# Edin_TinyPico_Nano.net
KiCad netlist of a schematic drawn in EAGLE
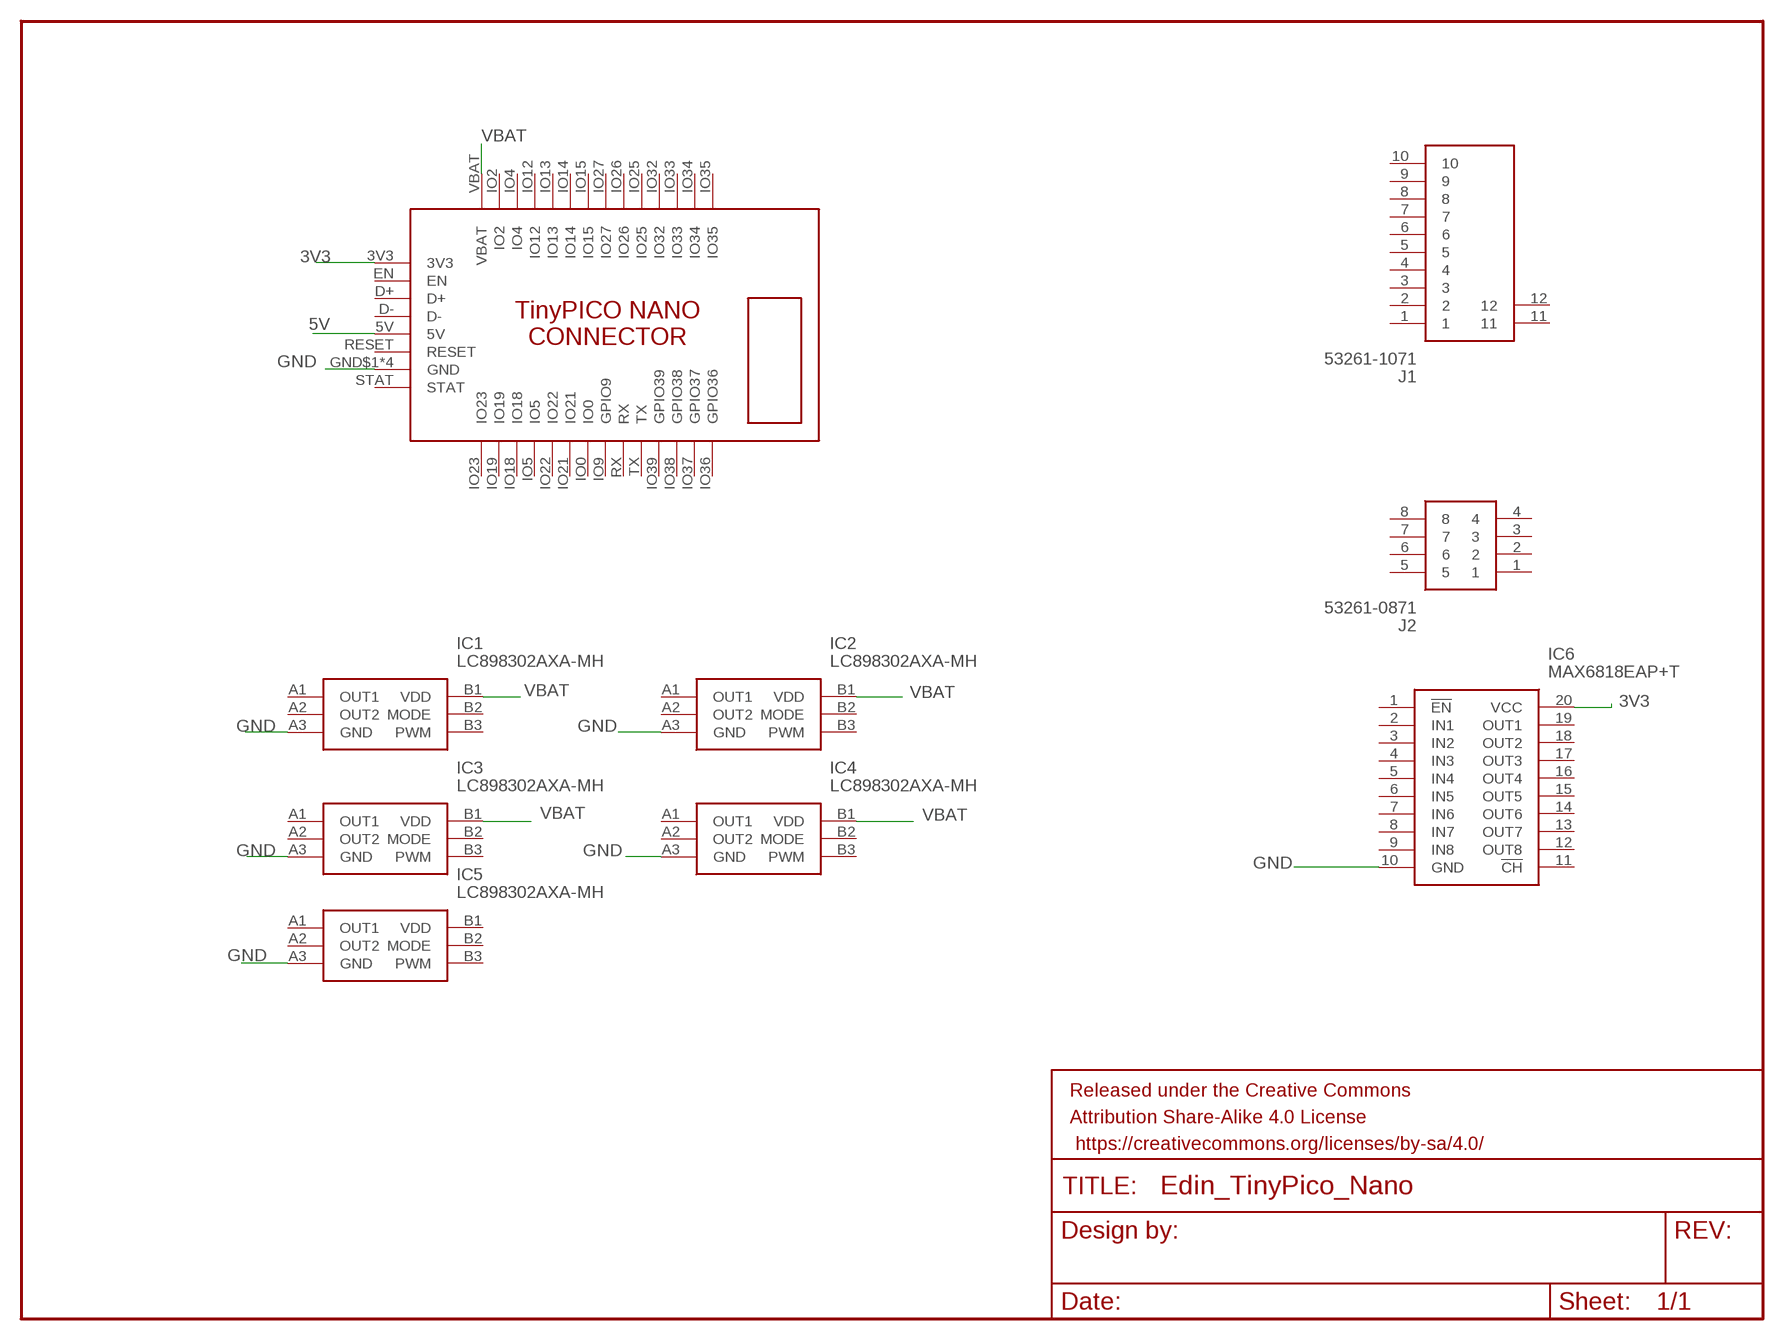
[diagram p0: schematic, sheet 1]

(export (version "E")
  (design (tool "Eeschema 10.0.6"))
  (components
    (comp (ref "FRAME1")
      (value "FRAME-LETTER")
      (footprint "eagle-import:CREATIVE_COMMONS")
      (libsource (lib "eagle-import") (part "FRAME-LETTER"))
    )
    (comp (ref "IC1")
      (value "LC898302AXA-MH")
      (footprint "eagle-import:BGA6C40P3X2_118X78X65")
      (fields (field (name "MOUSER_PART_NUMBER") "863-LC898302AXA-MH"))
      (libsource (lib "eagle-import") (part "LC898302AXA-MH"))
    )
    (comp (ref "IC2")
      (value "LC898302AXA-MH")
      (footprint "eagle-import:BGA6C40P3X2_118X78X65")
      (fields (field (name "MOUSER_PART_NUMBER") "863-LC898302AXA-MH"))
      (libsource (lib "eagle-import") (part "LC898302AXA-MH"))
    )
    (comp (ref "IC3")
      (value "LC898302AXA-MH")
      (footprint "eagle-import:BGA6C40P3X2_118X78X65")
      (fields (field (name "MOUSER_PART_NUMBER") "863-LC898302AXA-MH"))
      (libsource (lib "eagle-import") (part "LC898302AXA-MH"))
    )
    (comp (ref "IC4")
      (value "LC898302AXA-MH")
      (footprint "eagle-import:BGA6C40P3X2_118X78X65")
      (fields (field (name "MOUSER_PART_NUMBER") "863-LC898302AXA-MH"))
      (libsource (lib "eagle-import") (part "LC898302AXA-MH"))
    )
    (comp (ref "IC5")
      (value "LC898302AXA-MH")
      (footprint "eagle-import:BGA6C40P3X2_118X78X65")
      (fields (field (name "MOUSER_PART_NUMBER") "863-LC898302AXA-MH"))
      (libsource (lib "eagle-import") (part "LC898302AXA-MH"))
    )
    (comp (ref "IC6")
      (value "MAX6818EAP+T")
      (footprint "eagle-import:SOP65P778X199-20N")
      (fields (field (name "MOUSER_PART_NUMBER") "700-MAX6818EAPT"))
      (libsource (lib "eagle-import") (part "MAX6818EAP+T"))
    )
    (comp (ref "J1")
      (value "53261-1071")
      (footprint "eagle-import:532611071")
      (fields (field (name "MOUSER_PART_NUMBER") "538-53261-1071"))
      (libsource (lib "eagle-import") (part "53261-1071"))
    )
    (comp (ref "J2")
      (value "53261-0871")
      (footprint "eagle-import:53261-0871")
      (fields (field (name "MOUSER_PART_NUMBER") "538-53261-0871"))
      (libsource (lib "eagle-import") (part "53261-0871"))
    )
    (comp (ref "U$1")
      (value "TINYPICO-NANO-CONNECTOR")
      (footprint "eagle-import:TINYPICO-NANO-CONNECTOR")
      (libsource (lib "eagle-import") (part "TINYPICO-NANO-CONNECTOR"))
    )
  )
  (nets
    (net (code "1") (name "/3V3") (class "Default")
      (node (ref "IC6") (pin "20") (pinfunction "VCC_20") (pintype "power_in"))
      (node (ref "U$1") (pin "3V3") (pinfunction "3V3_3V3") (pintype "power_in"))
    )
    (net (code "2") (name "/5V") (class "Default")
      (node (ref "U$1") (pin "5V") (pinfunction "5V_5V") (pintype "power_in"))
    )
    (net (code "3") (name "/GND") (class "Default")
      (node (ref "IC1") (pin "A3") (pinfunction "GND_A3") (pintype "bidirectional"))
      (node (ref "IC2") (pin "A3") (pinfunction "GND_A3") (pintype "bidirectional"))
      (node (ref "IC3") (pin "A3") (pinfunction "GND_A3") (pintype "bidirectional"))
      (node (ref "IC4") (pin "A3") (pinfunction "GND_A3") (pintype "bidirectional"))
      (node (ref "IC5") (pin "A3") (pinfunction "GND_A3") (pintype "bidirectional"))
      (node (ref "IC6") (pin "10") (pinfunction "GND_10") (pintype "power_in"))
      (node (ref "U$1") (pin "GND$1") (pinfunction "GND_GND$1") (pintype "power_in"))
      (node (ref "U$1") (pin "GND$2") (pinfunction "GND_GND$2") (pintype "power_in"))
      (node (ref "U$1") (pin "GND$3") (pinfunction "GND_GND$3") (pintype "power_in"))
      (node (ref "U$1") (pin "GND$4") (pinfunction "GND_GND$4") (pintype "power_in"))
    )
    (net (code "4") (name "/VBAT") (class "Default")
      (node (ref "IC1") (pin "B1") (pinfunction "VDD_B1") (pintype "bidirectional"))
      (node (ref "IC2") (pin "B1") (pinfunction "VDD_B1") (pintype "bidirectional"))
      (node (ref "IC3") (pin "B1") (pinfunction "VDD_B1") (pintype "bidirectional"))
      (node (ref "IC4") (pin "B1") (pinfunction "VDD_B1") (pintype "bidirectional"))
      (node (ref "U$1") (pin "VBAT") (pinfunction "VBAT_VBAT") (pintype "power_in"))
    )
    (net (code "5") (name "unconnected-(IC1-MODE-PadB2)") (class "Default")
      (node (ref "IC1") (pin "B2") (pinfunction "MODE_B2") (pintype "bidirectional"))
    )
    (net (code "6") (name "unconnected-(IC1-OUT1-PadA1)") (class "Default")
      (node (ref "IC1") (pin "A1") (pinfunction "OUT1_A1") (pintype "bidirectional"))
    )
    (net (code "7") (name "unconnected-(IC1-OUT2-PadA2)") (class "Default")
      (node (ref "IC1") (pin "A2") (pinfunction "OUT2_A2") (pintype "bidirectional"))
    )
    (net (code "8") (name "unconnected-(IC1-PWM-PadB3)") (class "Default")
      (node (ref "IC1") (pin "B3") (pinfunction "PWM_B3") (pintype "bidirectional"))
    )
    (net (code "9") (name "unconnected-(IC2-MODE-PadB2)") (class "Default")
      (node (ref "IC2") (pin "B2") (pinfunction "MODE_B2") (pintype "bidirectional"))
    )
    (net (code "10") (name "unconnected-(IC2-OUT1-PadA1)") (class "Default")
      (node (ref "IC2") (pin "A1") (pinfunction "OUT1_A1") (pintype "bidirectional"))
    )
    (net (code "11") (name "unconnected-(IC2-OUT2-PadA2)") (class "Default")
      (node (ref "IC2") (pin "A2") (pinfunction "OUT2_A2") (pintype "bidirectional"))
    )
    (net (code "12") (name "unconnected-(IC2-PWM-PadB3)") (class "Default")
      (node (ref "IC2") (pin "B3") (pinfunction "PWM_B3") (pintype "bidirectional"))
    )
    (net (code "13") (name "unconnected-(IC3-MODE-PadB2)") (class "Default")
      (node (ref "IC3") (pin "B2") (pinfunction "MODE_B2") (pintype "bidirectional"))
    )
    (net (code "14") (name "unconnected-(IC3-OUT1-PadA1)") (class "Default")
      (node (ref "IC3") (pin "A1") (pinfunction "OUT1_A1") (pintype "bidirectional"))
    )
    (net (code "15") (name "unconnected-(IC3-OUT2-PadA2)") (class "Default")
      (node (ref "IC3") (pin "A2") (pinfunction "OUT2_A2") (pintype "bidirectional"))
    )
    (net (code "16") (name "unconnected-(IC3-PWM-PadB3)") (class "Default")
      (node (ref "IC3") (pin "B3") (pinfunction "PWM_B3") (pintype "bidirectional"))
    )
    (net (code "17") (name "unconnected-(IC4-MODE-PadB2)") (class "Default")
      (node (ref "IC4") (pin "B2") (pinfunction "MODE_B2") (pintype "bidirectional"))
    )
    (net (code "18") (name "unconnected-(IC4-OUT1-PadA1)") (class "Default")
      (node (ref "IC4") (pin "A1") (pinfunction "OUT1_A1") (pintype "bidirectional"))
    )
    (net (code "19") (name "unconnected-(IC4-OUT2-PadA2)") (class "Default")
      (node (ref "IC4") (pin "A2") (pinfunction "OUT2_A2") (pintype "bidirectional"))
    )
    (net (code "20") (name "unconnected-(IC4-PWM-PadB3)") (class "Default")
      (node (ref "IC4") (pin "B3") (pinfunction "PWM_B3") (pintype "bidirectional"))
    )
    (net (code "21") (name "unconnected-(IC5-MODE-PadB2)") (class "Default")
      (node (ref "IC5") (pin "B2") (pinfunction "MODE_B2") (pintype "bidirectional"))
    )
    (net (code "22") (name "unconnected-(IC5-OUT1-PadA1)") (class "Default")
      (node (ref "IC5") (pin "A1") (pinfunction "OUT1_A1") (pintype "bidirectional"))
    )
    (net (code "23") (name "unconnected-(IC5-OUT2-PadA2)") (class "Default")
      (node (ref "IC5") (pin "A2") (pinfunction "OUT2_A2") (pintype "bidirectional"))
    )
    (net (code "24") (name "unconnected-(IC5-PWM-PadB3)") (class "Default")
      (node (ref "IC5") (pin "B3") (pinfunction "PWM_B3") (pintype "bidirectional"))
    )
    (net (code "25") (name "unconnected-(IC5-VDD-PadB1)") (class "Default")
      (node (ref "IC5") (pin "B1") (pinfunction "VDD_B1") (pintype "bidirectional"))
    )
    (net (code "26") (name "unconnected-(IC6-IN1-Pad2)") (class "Default")
      (node (ref "IC6") (pin "2") (pinfunction "IN1_2") (pintype "input"))
    )
    (net (code "27") (name "unconnected-(IC6-IN2-Pad3)") (class "Default")
      (node (ref "IC6") (pin "3") (pinfunction "IN2_3") (pintype "input"))
    )
    (net (code "28") (name "unconnected-(IC6-IN3-Pad4)") (class "Default")
      (node (ref "IC6") (pin "4") (pinfunction "IN3_4") (pintype "input"))
    )
    (net (code "29") (name "unconnected-(IC6-IN4-Pad5)") (class "Default")
      (node (ref "IC6") (pin "5") (pinfunction "IN4_5") (pintype "input"))
    )
    (net (code "30") (name "unconnected-(IC6-IN5-Pad6)") (class "Default")
      (node (ref "IC6") (pin "6") (pinfunction "IN5_6") (pintype "input"))
    )
    (net (code "31") (name "unconnected-(IC6-IN6-Pad7)") (class "Default")
      (node (ref "IC6") (pin "7") (pinfunction "IN6_7") (pintype "input"))
    )
    (net (code "32") (name "unconnected-(IC6-IN7-Pad8)") (class "Default")
      (node (ref "IC6") (pin "8") (pinfunction "IN7_8") (pintype "input"))
    )
    (net (code "33") (name "unconnected-(IC6-IN8-Pad9)") (class "Default")
      (node (ref "IC6") (pin "9") (pinfunction "IN8_9") (pintype "input"))
    )
    (net (code "34") (name "unconnected-(IC6-OUT1-Pad19)") (class "Default")
      (node (ref "IC6") (pin "19") (pinfunction "OUT1_19") (pintype "output"))
    )
    (net (code "35") (name "unconnected-(IC6-OUT2-Pad18)") (class "Default")
      (node (ref "IC6") (pin "18") (pinfunction "OUT2_18") (pintype "output"))
    )
    (net (code "36") (name "unconnected-(IC6-OUT3-Pad17)") (class "Default")
      (node (ref "IC6") (pin "17") (pinfunction "OUT3_17") (pintype "output"))
    )
    (net (code "37") (name "unconnected-(IC6-OUT4-Pad16)") (class "Default")
      (node (ref "IC6") (pin "16") (pinfunction "OUT4_16") (pintype "output"))
    )
    (net (code "38") (name "unconnected-(IC6-OUT5-Pad15)") (class "Default")
      (node (ref "IC6") (pin "15") (pinfunction "OUT5_15") (pintype "output"))
    )
    (net (code "39") (name "unconnected-(IC6-OUT6-Pad14)") (class "Default")
      (node (ref "IC6") (pin "14") (pinfunction "OUT6_14") (pintype "output"))
    )
    (net (code "40") (name "unconnected-(IC6-OUT7-Pad13)") (class "Default")
      (node (ref "IC6") (pin "13") (pinfunction "OUT7_13") (pintype "output"))
    )
    (net (code "41") (name "unconnected-(IC6-OUT8-Pad12)") (class "Default")
      (node (ref "IC6") (pin "12") (pinfunction "OUT8_12") (pintype "output"))
    )
    (net (code "42") (name "unconnected-(IC6-~{CH}-Pad11)") (class "Default")
      (node (ref "IC6") (pin "11") (pinfunction "~{CH}_11") (pintype "output"))
    )
    (net (code "43") (name "unconnected-(IC6-~{EN}-Pad1)") (class "Default")
      (node (ref "IC6") (pin "1") (pinfunction "~{EN}_1") (pintype "input"))
    )
    (net (code "44") (name "unconnected-(J1-Pad1)") (class "Default")
      (node (ref "J1") (pin "1") (pinfunction "1_1") (pintype "bidirectional"))
    )
    (net (code "45") (name "unconnected-(J1-Pad2)") (class "Default")
      (node (ref "J1") (pin "2") (pinfunction "2_2") (pintype "bidirectional"))
    )
    (net (code "46") (name "unconnected-(J1-Pad3)") (class "Default")
      (node (ref "J1") (pin "3") (pinfunction "3_3") (pintype "bidirectional"))
    )
    (net (code "47") (name "unconnected-(J1-Pad4)") (class "Default")
      (node (ref "J1") (pin "4") (pinfunction "4_4") (pintype "bidirectional"))
    )
    (net (code "48") (name "unconnected-(J1-Pad5)") (class "Default")
      (node (ref "J1") (pin "5") (pinfunction "5_5") (pintype "bidirectional"))
    )
    (net (code "49") (name "unconnected-(J1-Pad6)") (class "Default")
      (node (ref "J1") (pin "6") (pinfunction "6_6") (pintype "bidirectional"))
    )
    (net (code "50") (name "unconnected-(J1-Pad7)") (class "Default")
      (node (ref "J1") (pin "7") (pinfunction "7_7") (pintype "bidirectional"))
    )
    (net (code "51") (name "unconnected-(J1-Pad8)") (class "Default")
      (node (ref "J1") (pin "8") (pinfunction "8_8") (pintype "bidirectional"))
    )
    (net (code "52") (name "unconnected-(J1-Pad9)") (class "Default")
      (node (ref "J1") (pin "9") (pinfunction "9_9") (pintype "bidirectional"))
    )
    (net (code "53") (name "unconnected-(J1-Pad10)") (class "Default")
      (node (ref "J1") (pin "10") (pinfunction "10_10") (pintype "bidirectional"))
    )
    (net (code "54") (name "unconnected-(J1-Pad11)") (class "Default")
      (node (ref "J1") (pin "11") (pinfunction "11_11") (pintype "bidirectional"))
    )
    (net (code "55") (name "unconnected-(J1-Pad12)") (class "Default")
      (node (ref "J1") (pin "12") (pinfunction "12_12") (pintype "bidirectional"))
    )
    (net (code "56") (name "unconnected-(J2-Pad1)") (class "Default")
      (node (ref "J2") (pin "1") (pinfunction "1_1") (pintype "bidirectional"))
    )
    (net (code "57") (name "unconnected-(J2-Pad2)") (class "Default")
      (node (ref "J2") (pin "2") (pinfunction "2_2") (pintype "bidirectional"))
    )
    (net (code "58") (name "unconnected-(J2-Pad3)") (class "Default")
      (node (ref "J2") (pin "3") (pinfunction "3_3") (pintype "bidirectional"))
    )
    (net (code "59") (name "unconnected-(J2-Pad4)") (class "Default")
      (node (ref "J2") (pin "4") (pinfunction "4_4") (pintype "bidirectional"))
    )
    (net (code "60") (name "unconnected-(J2-Pad5)") (class "Default")
      (node (ref "J2") (pin "5") (pinfunction "5_5") (pintype "bidirectional"))
    )
    (net (code "61") (name "unconnected-(J2-Pad6)") (class "Default")
      (node (ref "J2") (pin "6") (pinfunction "6_6") (pintype "bidirectional"))
    )
    (net (code "62") (name "unconnected-(J2-Pad7)") (class "Default")
      (node (ref "J2") (pin "7") (pinfunction "7_7") (pintype "bidirectional"))
    )
    (net (code "63") (name "unconnected-(J2-Pad8)") (class "Default")
      (node (ref "J2") (pin "8") (pinfunction "8_8") (pintype "bidirectional"))
    )
    (net (code "64") (name "unconnected-(U$1-GPIO9-PadIO9)") (class "Default")
      (node (ref "U$1") (pin "IO9") (pinfunction "GPIO9_IO9") (pintype "bidirectional"))
    )
    (net (code "65") (name "unconnected-(U$1-GPIO36-PadIO36)") (class "Default")
      (node (ref "U$1") (pin "IO36") (pinfunction "GPIO36_IO36") (pintype "bidirectional"))
    )
    (net (code "66") (name "unconnected-(U$1-GPIO37-PadIO37)") (class "Default")
      (node (ref "U$1") (pin "IO37") (pinfunction "GPIO37_IO37") (pintype "bidirectional"))
    )
    (net (code "67") (name "unconnected-(U$1-GPIO38-PadIO38)") (class "Default")
      (node (ref "U$1") (pin "IO38") (pinfunction "GPIO38_IO38") (pintype "bidirectional"))
    )
    (net (code "68") (name "unconnected-(U$1-GPIO39-PadIO39)") (class "Default")
      (node (ref "U$1") (pin "IO39") (pinfunction "GPIO39_IO39") (pintype "bidirectional"))
    )
    (net (code "69") (name "unconnected-(U$1-PadD+)") (class "Default")
      (node (ref "U$1") (pin "D+") (pinfunction "D+_D+") (pintype "bidirectional"))
    )
    (net (code "70") (name "unconnected-(U$1-PadD-)") (class "Default")
      (node (ref "U$1") (pin "D-") (pinfunction "D-_D-") (pintype "bidirectional"))
    )
    (net (code "71") (name "unconnected-(U$1-PadEN)") (class "Default")
      (node (ref "U$1") (pin "EN") (pinfunction "EN_EN") (pintype "input"))
    )
    (net (code "72") (name "unconnected-(U$1-PadIO0)") (class "Default")
      (node (ref "U$1") (pin "IO0") (pinfunction "IO0_IO0") (pintype "bidirectional"))
    )
    (net (code "73") (name "unconnected-(U$1-PadIO2)") (class "Default")
      (node (ref "U$1") (pin "IO2") (pinfunction "IO2_IO2") (pintype "bidirectional"))
    )
    (net (code "74") (name "unconnected-(U$1-PadIO4)") (class "Default")
      (node (ref "U$1") (pin "IO4") (pinfunction "IO4_IO4") (pintype "bidirectional"))
    )
    (net (code "75") (name "unconnected-(U$1-PadIO5)") (class "Default")
      (node (ref "U$1") (pin "IO5") (pinfunction "IO5_IO5") (pintype "bidirectional"))
    )
    (net (code "76") (name "unconnected-(U$1-PadIO12)") (class "Default")
      (node (ref "U$1") (pin "IO12") (pinfunction "IO12_IO12") (pintype "bidirectional"))
    )
    (net (code "77") (name "unconnected-(U$1-PadIO13)") (class "Default")
      (node (ref "U$1") (pin "IO13") (pinfunction "IO13_IO13") (pintype "bidirectional"))
    )
    (net (code "78") (name "unconnected-(U$1-PadIO14)") (class "Default")
      (node (ref "U$1") (pin "IO14") (pinfunction "IO14_IO14") (pintype "bidirectional"))
    )
    (net (code "79") (name "unconnected-(U$1-PadIO15)") (class "Default")
      (node (ref "U$1") (pin "IO15") (pinfunction "IO15_IO15") (pintype "bidirectional"))
    )
    (net (code "80") (name "unconnected-(U$1-PadIO18)") (class "Default")
      (node (ref "U$1") (pin "IO18") (pinfunction "IO18_IO18") (pintype "bidirectional"))
    )
    (net (code "81") (name "unconnected-(U$1-PadIO19)") (class "Default")
      (node (ref "U$1") (pin "IO19") (pinfunction "IO19_IO19") (pintype "bidirectional"))
    )
    (net (code "82") (name "unconnected-(U$1-PadIO21)") (class "Default")
      (node (ref "U$1") (pin "IO21") (pinfunction "IO21_IO21") (pintype "bidirectional"))
    )
    (net (code "83") (name "unconnected-(U$1-PadIO22)") (class "Default")
      (node (ref "U$1") (pin "IO22") (pinfunction "IO22_IO22") (pintype "bidirectional"))
    )
    (net (code "84") (name "unconnected-(U$1-PadIO23)") (class "Default")
      (node (ref "U$1") (pin "IO23") (pinfunction "IO23_IO23") (pintype "bidirectional"))
    )
    (net (code "85") (name "unconnected-(U$1-PadIO25)") (class "Default")
      (node (ref "U$1") (pin "IO25") (pinfunction "IO25_IO25") (pintype "bidirectional"))
    )
    (net (code "86") (name "unconnected-(U$1-PadIO26)") (class "Default")
      (node (ref "U$1") (pin "IO26") (pinfunction "IO26_IO26") (pintype "bidirectional"))
    )
    (net (code "87") (name "unconnected-(U$1-PadIO27)") (class "Default")
      (node (ref "U$1") (pin "IO27") (pinfunction "IO27_IO27") (pintype "bidirectional"))
    )
    (net (code "88") (name "unconnected-(U$1-PadIO32)") (class "Default")
      (node (ref "U$1") (pin "IO32") (pinfunction "IO32_IO32") (pintype "bidirectional"))
    )
    (net (code "89") (name "unconnected-(U$1-PadIO33)") (class "Default")
      (node (ref "U$1") (pin "IO33") (pinfunction "IO33_IO33") (pintype "bidirectional"))
    )
    (net (code "90") (name "unconnected-(U$1-PadIO34)") (class "Default")
      (node (ref "U$1") (pin "IO34") (pinfunction "IO34_IO34") (pintype "bidirectional"))
    )
    (net (code "91") (name "unconnected-(U$1-PadIO35)") (class "Default")
      (node (ref "U$1") (pin "IO35") (pinfunction "IO35_IO35") (pintype "bidirectional"))
    )
    (net (code "92") (name "unconnected-(U$1-PadRESET)") (class "Default")
      (node (ref "U$1") (pin "RESET") (pinfunction "RESET_RESET") (pintype "bidirectional"))
    )
    (net (code "93") (name "unconnected-(U$1-PadRX)") (class "Default")
      (node (ref "U$1") (pin "RX") (pinfunction "RX_RX") (pintype "bidirectional"))
    )
    (net (code "94") (name "unconnected-(U$1-PadSTAT)") (class "Default")
      (node (ref "U$1") (pin "STAT") (pinfunction "STAT_STAT") (pintype "output"))
    )
    (net (code "95") (name "unconnected-(U$1-PadTX)") (class "Default")
      (node (ref "U$1") (pin "TX") (pinfunction "TX_TX") (pintype "bidirectional"))
    )
  )
)
